# v847_redraw.net
KiCad netlist of a schematic drawn in EAGLE
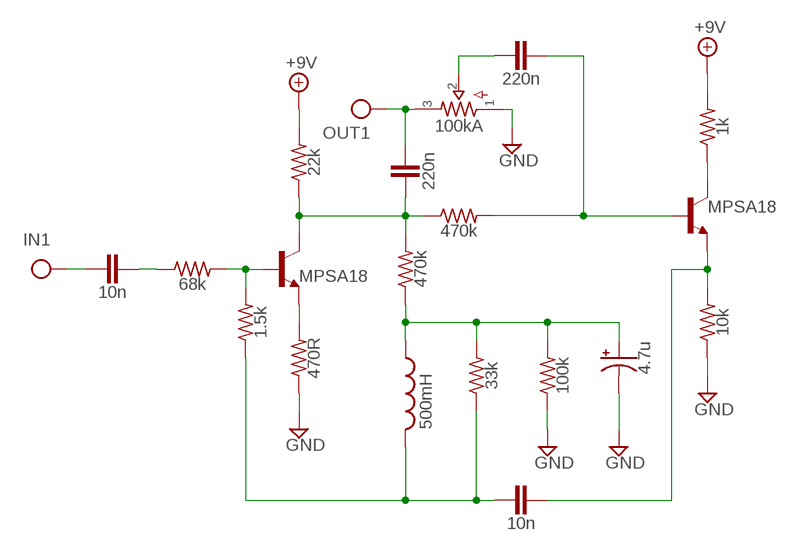
[diagram p0: schematic, sheet 1]

(export (version "E")
  (design (tool "Eeschema 10.0.6"))
  (components
    (comp (ref "C1")
      (value "10n")
      (footprint "eagle-import:BOX_SMALL")
      (libsource (lib "eagle-import") (part "CER/FILMBOX.1"))
    )
    (comp (ref "C106")
      (value "220n")
      (footprint "eagle-import:050X030_025")
      (libsource (lib "eagle-import") (part "CER/FILM1"))
    )
    (comp (ref "C107")
      (value "220n")
      (footprint "eagle-import:BOX_SMALL")
      (libsource (lib "eagle-import") (part "CER/FILMBOX.1"))
    )
    (comp (ref "C108")
      (value "10n")
      (footprint "eagle-import:BOX_SMALL")
      (libsource (lib "eagle-import") (part "CER/FILMBOX.1"))
    )
    (comp (ref "C109")
      (value "4.7u")
      (footprint "eagle-import:050_020")
      (libsource (lib "eagle-import") (part "0500"))
    )
    (comp (ref "L101")
      (value "500mH")
      (footprint "eagle-import:WAH")
      (libsource (lib "eagle-import") (part "WAH"))
    )
    (comp (ref "POT101")
      (value "100kA")
      (footprint "eagle-import:16MM")
      (libsource (lib "eagle-import") (part "POTS16MM"))
    )
    (comp (ref "Q102")
      (value "MPSA18")
      (footprint "eagle-import:TO92-")
      (libsource (lib "eagle-import") (part "MPSA18"))
    )
    (comp (ref "Q103")
      (value "MPSA18")
      (footprint "eagle-import:TO92-")
      (libsource (lib "eagle-import") (part "MPSA18"))
    )
    (comp (ref "R104")
      (value "68k")
      (footprint "eagle-import:R0207_3")
      (libsource (lib "eagle-import") (part "R_.3B"))
    )
    (comp (ref "R105")
      (value "1.5k")
      (footprint "eagle-import:R0207_3")
      (libsource (lib "eagle-import") (part "R_.3B"))
    )
    (comp (ref "R106")
      (value "22k")
      (footprint "eagle-import:R0207_3")
      (libsource (lib "eagle-import") (part "R_.3B"))
    )
    (comp (ref "R107")
      (value "470R")
      (footprint "eagle-import:R0207_3")
      (libsource (lib "eagle-import") (part "R_.3B"))
    )
    (comp (ref "R108")
      (value "470k")
      (footprint "eagle-import:R0207_3")
      (libsource (lib "eagle-import") (part "R_.3B"))
    )
    (comp (ref "R110")
      (value "470k")
      (footprint "eagle-import:R0207_3")
      (libsource (lib "eagle-import") (part "R_.3B"))
    )
    (comp (ref "R111")
      (value "33k")
      (footprint "eagle-import:R0207_3")
      (libsource (lib "eagle-import") (part "R_.3B"))
    )
    (comp (ref "R112")
      (value "100k")
      (footprint "eagle-import:R0207_3")
      (libsource (lib "eagle-import") (part "R_.3B"))
    )
    (comp (ref "R113")
      (value "1k")
      (footprint "eagle-import:R0207_3")
      (libsource (lib "eagle-import") (part "R_.3B"))
    )
    (comp (ref "R114")
      (value "10k")
      (footprint "eagle-import:R0207_3")
      (libsource (lib "eagle-import") (part "R_.3B"))
    )
  )
  (nets
    (net (code "1") (name "+9V") (class "Default")
      (node (ref "R106") (pin "2") (pinfunction "2_2") (pintype "passive"))
      (node (ref "R113") (pin "2") (pinfunction "2_2") (pintype "passive"))
    )
    (net (code "2") (name "GND") (class "Default")
      (node (ref "C109") (pin "-") (pinfunction "-_-") (pintype "passive"))
      (node (ref "POT101") (pin "1") (pinfunction "1_1") (pintype "passive"))
      (node (ref "R107") (pin "1") (pinfunction "1_1") (pintype "passive"))
      (node (ref "R112") (pin "1") (pinfunction "1_1") (pintype "passive"))
      (node (ref "R114") (pin "1") (pinfunction "1_1") (pintype "passive"))
    )
    (net (code "3") (name "IN") (class "Default")
      (node (ref "C1") (pin "2") (pinfunction "2_2") (pintype "passive"))
    )
    (net (code "4") (name "Net-(C1-Pad1)") (class "Default")
      (node (ref "C1") (pin "1") (pinfunction "1_1") (pintype "passive"))
      (node (ref "R104") (pin "1") (pinfunction "1_1") (pintype "passive"))
    )
    (net (code "5") (name "Net-(C107-Pad2)") (class "Default")
      (node (ref "C107") (pin "2") (pinfunction "2_2") (pintype "passive"))
      (node (ref "POT101") (pin "2") (pinfunction "2_2") (pintype "passive"))
    )
    (net (code "6") (name "Net-(C108-Pad2)") (class "Default")
      (node (ref "C108") (pin "2") (pinfunction "2_2") (pintype "passive"))
      (node (ref "L101") (pin "2") (pinfunction "2_2") (pintype "passive"))
      (node (ref "R105") (pin "1") (pinfunction "1_1") (pintype "passive"))
      (node (ref "R111") (pin "1") (pinfunction "1_1") (pintype "passive"))
    )
    (net (code "7") (name "Net-(C109-Pad+)") (class "Default")
      (node (ref "C109") (pin "+") (pinfunction "+_+") (pintype "passive"))
      (node (ref "L101") (pin "1") (pinfunction "1_1") (pintype "passive"))
      (node (ref "R108") (pin "1") (pinfunction "1_1") (pintype "passive"))
      (node (ref "R111") (pin "2") (pinfunction "2_2") (pintype "passive"))
      (node (ref "R112") (pin "2") (pinfunction "2_2") (pintype "passive"))
    )
    (net (code "8") (name "Net-(Q102-B)") (class "Default")
      (node (ref "Q102") (pin "2") (pinfunction "B_2") (pintype "passive"))
      (node (ref "R104") (pin "2") (pinfunction "2_2") (pintype "passive"))
      (node (ref "R105") (pin "2") (pinfunction "2_2") (pintype "passive"))
    )
    (net (code "9") (name "Net-(Q102-C)") (class "Default")
      (node (ref "C106") (pin "2") (pinfunction "2_2") (pintype "passive"))
      (node (ref "Q102") (pin "1") (pinfunction "C_1") (pintype "passive"))
      (node (ref "R106") (pin "1") (pinfunction "1_1") (pintype "passive"))
      (node (ref "R108") (pin "2") (pinfunction "2_2") (pintype "passive"))
      (node (ref "R110") (pin "1") (pinfunction "1_1") (pintype "passive"))
    )
    (net (code "10") (name "Net-(Q102-E)") (class "Default")
      (node (ref "Q102") (pin "3") (pinfunction "E_3") (pintype "passive"))
      (node (ref "R107") (pin "2") (pinfunction "2_2") (pintype "passive"))
    )
    (net (code "11") (name "Net-(Q103-B)") (class "Default")
      (node (ref "C107") (pin "1") (pinfunction "1_1") (pintype "passive"))
      (node (ref "Q103") (pin "2") (pinfunction "B_2") (pintype "passive"))
      (node (ref "R110") (pin "2") (pinfunction "2_2") (pintype "passive"))
    )
    (net (code "12") (name "Net-(Q103-C)") (class "Default")
      (node (ref "Q103") (pin "1") (pinfunction "C_1") (pintype "passive"))
      (node (ref "R113") (pin "1") (pinfunction "1_1") (pintype "passive"))
    )
    (net (code "13") (name "Net-(Q103-E)") (class "Default")
      (node (ref "C108") (pin "1") (pinfunction "1_1") (pintype "passive"))
      (node (ref "Q103") (pin "3") (pinfunction "E_3") (pintype "passive"))
      (node (ref "R114") (pin "2") (pinfunction "2_2") (pintype "passive"))
    )
    (net (code "14") (name "OUT") (class "Default")
      (node (ref "C106") (pin "1") (pinfunction "1_1") (pintype "passive"))
      (node (ref "POT101") (pin "3") (pinfunction "3_3") (pintype "passive"))
    )
  )
)
